# Output.net
KiCad netlist of a schematic drawn in Altium Designer
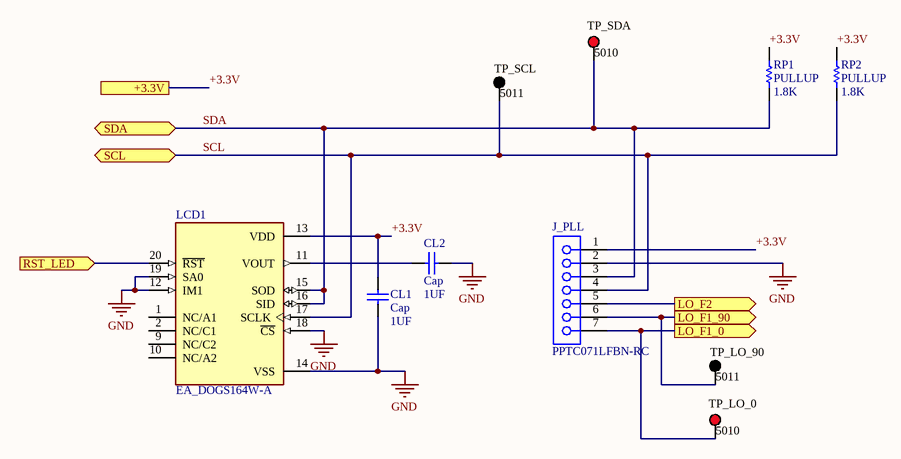
[diagram p0: Output.SchDoc]

(export (version "E")
  (design (tool "Eeschema 10.0.6"))
  (components
    (comp (ref "CL1")
      (value "Cap")
      (footprint "RADIAL-0.1")
      (description "Capacitor")
      (fields
        (field (name "MANUFACTURER PART NUMBER") "ESE105M100AC3EA")
        (field (name "ALTIUM_VALUE") "1UF")
        (field (name "PUBLISHER") "Altium Limited")
      )
      (libsource (lib "ECE295-Capacitors-TH") (part "CAP ALUM 1UF 20% 100V RADIAL"))
    )
    (comp (ref "CL2")
      (value "Cap")
      (footprint "RADIAL-0.1")
      (description "Capacitor")
      (fields
        (field (name "MANUFACTURER PART NUMBER") "ESE105M100AC3EA")
        (field (name "ALTIUM_VALUE") "1UF")
        (field (name "PUBLISHER") "Altium Limited")
      )
      (libsource (lib "ECE295-Capacitors-TH") (part "CAP ALUM 1UF 20% 100V RADIAL"))
    )
    (comp (ref "J_PLL")
      (value "PPTC071LFBN-RC")
      (footprint "SMTC-SSQ-107-01-X-S")
      (description "SQ Post Socket, Through-hole, Vertical, -55 to 125 degC, 2.54 mm Pitch, 7-Pin, Female, RoHS")
      (fields (field (name "PARTNUMBER") "SSQ-107-01-G-S") (field (name "MANUFACTURER") "Samtec"))
      (libsource (lib "Altium Content Vault") (part "SMTC-SSQ-107-01-X-S"))
    )
    (comp (ref "LCD1")
      (value "EA_DOGS164W-A")
      (footprint "LCD_EA_DOGS164W-A")
      (fields (field (name "MF") "Display Visions") (field (name "MP") "EA DOGS164W-A"))
      (libsource (lib "EA_DOGS164W-A") (part "EA_DOGS164W-A"))
    )
    (comp (ref "RP1")
      (value "PULLUP")
      (footprint "AXIAL-0.1-RES")
      (description "Resistor")
      (fields
        (field (name "ALTIUM_VALUE") "1.8K")
        (field (name "MANUFACTURER PART NUMBER") "CFR-25JB-52-1K8")
        (field (name "TOLERANCE") "0.05")
        (field (name "PUBLISHER") "Altium Limited")
      )
      (libsource (lib "ECE295-Resistors-TH") (part "RES 1.8K OHM 5% 1/4W AXIAL"))
    )
    (comp (ref "RP2")
      (value "PULLUP")
      (footprint "AXIAL-0.1-RES")
      (description "Resistor")
      (fields
        (field (name "ALTIUM_VALUE") "1.8K")
        (field (name "MANUFACTURER PART NUMBER") "CFR-25JB-52-1K8")
        (field (name "TOLERANCE") "0.05")
        (field (name "PUBLISHER") "Altium Limited")
      )
      (libsource (lib "ECE295-Resistors-TH") (part "RES 1.8K OHM 5% 1/4W AXIAL"))
    )
    (comp (ref "TP_LO_0")
      (value "5010")
      (footprint "KSTN-5010_V")
      (description "Test Point, Red, Through Hole, RoHS, Bulk")
      (fields (field (name "MANUFACTURER") "Keystone"))
      (libsource (lib "Altium Content Vault") (part "TESTPOINT_RED"))
    )
    (comp (ref "TP_LO_90")
      (value "5011")
      (footprint "KSTN-5011_V")
      (description "Test Point, Black, Through Hole, RoHS, Bulk")
      (fields (field (name "MANUFACTURER") "Keystone"))
      (libsource (lib "Altium Content Vault") (part "TESTPOINT_BLACK"))
    )
    (comp (ref "TP_SCL")
      (value "5011")
      (footprint "KSTN-5011_V")
      (description "Test Point, Black, Through Hole, RoHS, Bulk")
      (fields (field (name "MANUFACTURER") "Keystone"))
      (libsource (lib "Altium Content Vault") (part "TESTPOINT_BLACK"))
    )
    (comp (ref "TP_SDA")
      (value "5010")
      (footprint "KSTN-5010_V")
      (description "Test Point, Red, Through Hole, RoHS, Bulk")
      (fields (field (name "MANUFACTURER") "Keystone"))
      (libsource (lib "Altium Content Vault") (part "TESTPOINT_RED"))
    )
  )
  (nets
    (net (code "1") (name "/+3.3V") (class "Default")
      (node (ref "CL1") (pin "2") (pinfunction "2_2") (pintype "passive"))
      (node (ref "J_PLL") (pin "1") (pinfunction "1_1") (pintype "passive"))
      (node (ref "LCD1") (pin "13") (pinfunction "VDD_13") (pintype "power_in"))
      (node (ref "RP1") (pin "2") (pinfunction "2_2") (pintype "passive"))
      (node (ref "RP2") (pin "2") (pinfunction "2_2") (pintype "passive"))
    )
    (net (code "2") (name "/LO_F1_0") (class "Default")
      (node (ref "J_PLL") (pin "7") (pinfunction "7_7") (pintype "passive"))
      (node (ref "TP_LO_0") (pin "1") (pinfunction "1_1") (pintype "passive"))
    )
    (net (code "3") (name "/LO_F1_90") (class "Default")
      (node (ref "J_PLL") (pin "6") (pinfunction "6_6") (pintype "passive"))
      (node (ref "TP_LO_90") (pin "1") (pinfunction "1_1") (pintype "passive"))
    )
    (net (code "4") (name "/LO_F2") (class "Default")
      (node (ref "J_PLL") (pin "5") (pinfunction "5_5") (pintype "passive"))
    )
    (net (code "5") (name "/RST_LED") (class "Default")
      (node (ref "LCD1") (pin "20") (pinfunction "~{RST}_20") (pintype "input"))
    )
    (net (code "6") (name "/SCL") (class "Default")
      (node (ref "J_PLL") (pin "4") (pinfunction "4_4") (pintype "passive"))
      (node (ref "LCD1") (pin "17") (pinfunction "SCLK_17") (pintype "input"))
      (node (ref "RP2") (pin "1") (pinfunction "1_1") (pintype "passive"))
      (node (ref "TP_SCL") (pin "1") (pinfunction "1_1") (pintype "passive"))
    )
    (net (code "7") (name "/SDA") (class "Default")
      (node (ref "J_PLL") (pin "3") (pinfunction "3_3") (pintype "passive"))
      (node (ref "LCD1") (pin "15") (pinfunction "SOD_15") (pintype "bidirectional"))
      (node (ref "LCD1") (pin "16") (pinfunction "SID_16") (pintype "bidirectional"))
      (node (ref "RP1") (pin "1") (pinfunction "1_1") (pintype "passive"))
      (node (ref "TP_SDA") (pin "1") (pinfunction "1_1") (pintype "passive"))
    )
    (net (code "8") (name "GND") (class "Default")
      (node (ref "CL1") (pin "1") (pinfunction "1_1") (pintype "passive"))
      (node (ref "CL2") (pin "1") (pinfunction "1_1") (pintype "passive"))
      (node (ref "J_PLL") (pin "2") (pinfunction "2_2") (pintype "passive"))
      (node (ref "LCD1") (pin "12") (pinfunction "IM1_12") (pintype "input"))
      (node (ref "LCD1") (pin "14") (pinfunction "VSS_14") (pintype "power_in"))
      (node (ref "LCD1") (pin "18") (pinfunction "~{CS}_18") (pintype "input"))
      (node (ref "LCD1") (pin "19") (pinfunction "SA0_19") (pintype "input"))
    )
    (net (code "9") (name "Net-(LCD1-VOUT)") (class "Default")
      (node (ref "CL2") (pin "2") (pinfunction "2_2") (pintype "passive"))
      (node (ref "LCD1") (pin "11") (pinfunction "VOUT_11") (pintype "output"))
    )
    (net (code "10") (name "unconnected-(LCD1-NC{slash}A1-Pad1)") (class "Default")
      (node (ref "LCD1") (pin "1") (pinfunction "NC/A1_1") (pintype "passive"))
    )
    (net (code "11") (name "unconnected-(LCD1-NC{slash}A2-Pad10)") (class "Default")
      (node (ref "LCD1") (pin "10") (pinfunction "NC/A2_10") (pintype "passive"))
    )
    (net (code "12") (name "unconnected-(LCD1-NC{slash}C1-Pad2)") (class "Default")
      (node (ref "LCD1") (pin "2") (pinfunction "NC/C1_2") (pintype "passive"))
    )
    (net (code "13") (name "unconnected-(LCD1-NC{slash}C2-Pad9)") (class "Default")
      (node (ref "LCD1") (pin "9") (pinfunction "NC/C2_9") (pintype "passive"))
    )
  )
)
